# LC_BigOne_-_MainBlock.net
KiCad netlist of a schematic drawn in Altium Designer
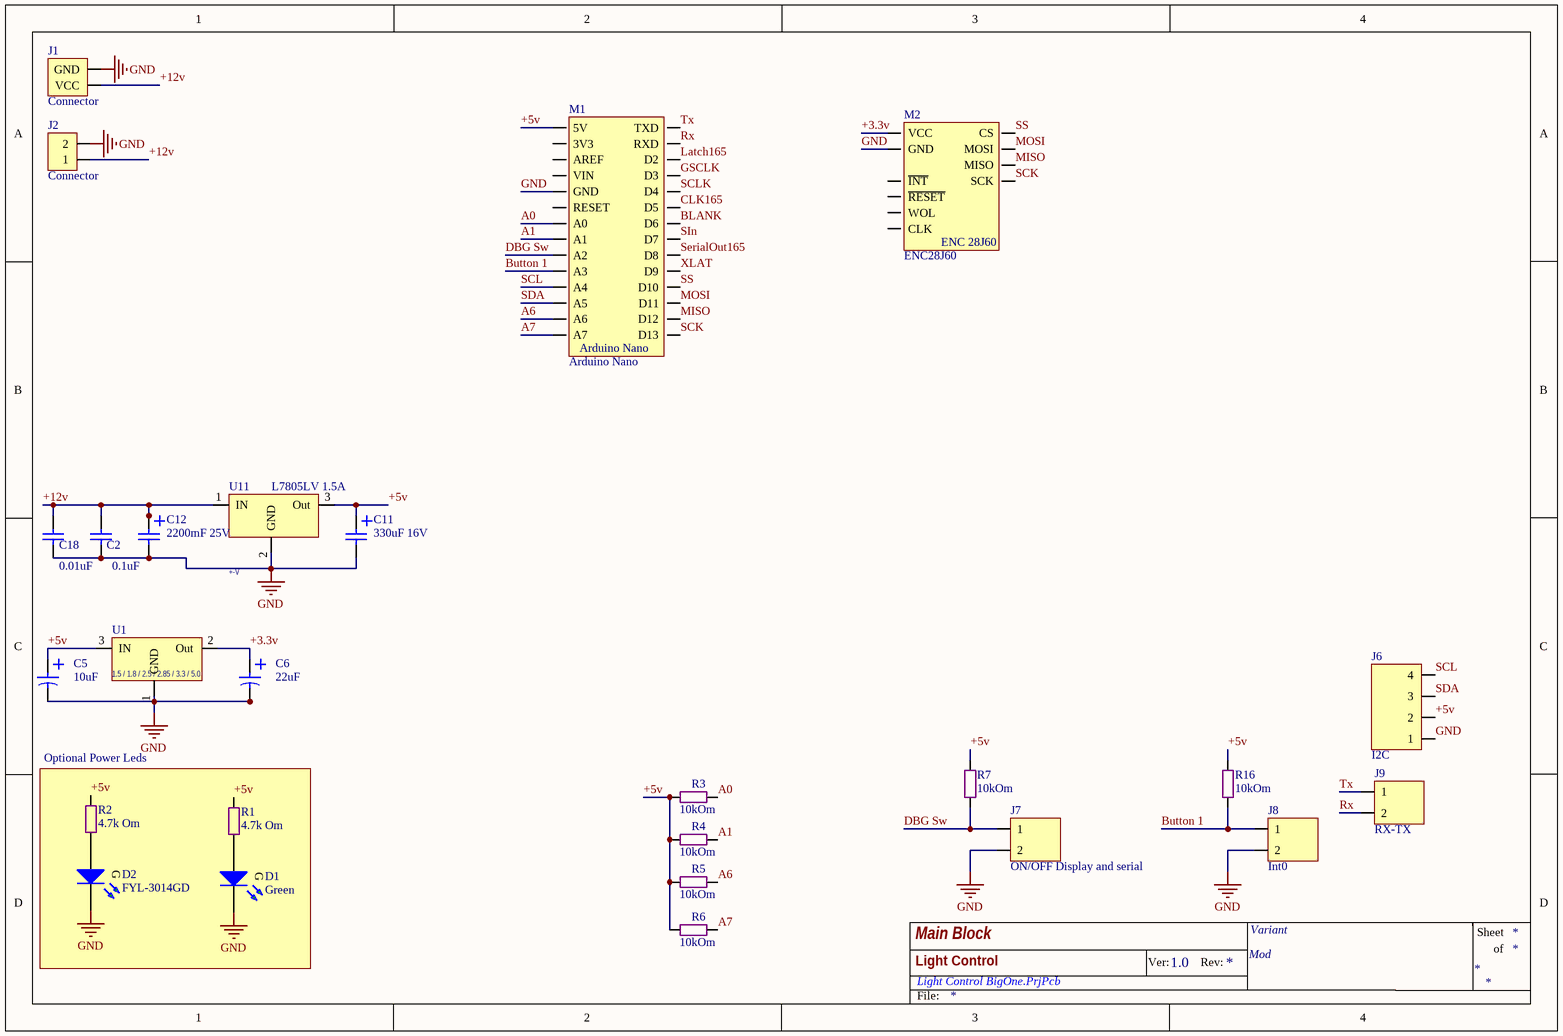
[diagram p0: LC BigOne - MainBlock.SchDoc]

(export (version "E")
  (design (tool "Eeschema 10.0.6"))
  (components
    (comp (ref "C2")
      (value "0.1uF")
      (footprint "Capacitor:SMD 0805 (2012)")
      (description "Capacitor")
      (libsource (lib "Capacitor") (part "Cap SMD 0402-1812"))
    )
    (comp (ref "C5")
      (value "10uF")
      (footprint "Capacitor:SMD 1206 Tantal (3216)")
      (description "Capacitor")
      (libsource (lib "Capacitor") (part "Cap Tantal"))
    )
    (comp (ref "C6")
      (value "22uF")
      (footprint "Capacitor:SMD 3528 Tantal (1210)")
      (description "Capacitor")
      (libsource (lib "Capacitor") (part "Cap Tantal"))
    )
    (comp (ref "C11")
      (value "330uF 16V")
      (footprint "Capacitor:Cap E p3.5mm D8xH12")
      (description "Capacitor")
      (libsource (lib "Capacitor") (part "Cap E 330uF x 16V"))
    )
    (comp (ref "C12")
      (value "2200mF 25V")
      (footprint "Capacitor:Cap E p5.08mm D10.2mm (3p) R")
      (description "Capacitor")
      (libsource (lib "Capacitor") (part "Cap E 2200mF x 16V"))
    )
    (comp (ref "C18")
      (value "0.01uF")
      (footprint "Capacitor:SMD 0805 (2012)")
      (description "Capacitor")
      (libsource (lib "Capacitor") (part "Cap SMD 0402-1812"))
    )
    (comp (ref "D1")
      (value "Green")
      (footprint "LED:LED SMD 0805 Green")
      (description "?2v ?20mA")
      (libsource (lib "LED") (part "Led SMD Green"))
    )
    (comp (ref "D2")
      (value "FYL-3014GD")
      (footprint "LED:LED Round 3mm Green")
      (description "2.1v 10mA, 15-30mCd")
      (libsource (lib "LED") (part "Led Round 3mm Green"))
    )
    (comp (ref "J1")
      (value "Connector")
      (footprint "Connector:DC Connector")
      (description "DC Connector")
      (libsource (lib "Connector") (part "DC Connector (PJ-002B)"))
    )
    (comp (ref "J2")
      (value "Connector")
      (footprint "Connector:DG301 5mm 2p")
      (description "DG301 series")
      (libsource (lib "Connector") (part "DG301-5.0-2P12"))
    )
    (comp (ref "J6")
      (value "I2C")
      (footprint "Connector:Line 2.54 X 4")
      (description "Vert, Sgl line, Male")
      (libsource (lib "Connector") (part "PLS-4"))
    )
    (comp (ref "J7")
      (value "ON/OFF Display and serial")
      (footprint "Connector:Line 2.54 x 2")
      (description "Vert, Sgl line, Male")
      (libsource (lib "Connector") (part "PLS-2"))
    )
    (comp (ref "J8")
      (value "Int0")
      (footprint "Connector:Line 2.54 x 2")
      (description "Vert, Sgl line, Male")
      (libsource (lib "Connector") (part "PLS-2"))
    )
    (comp (ref "J9")
      (value "RX-TX")
      (footprint "Connector:Line 2.54 x 2")
      (description "Vert, Sgl line, Male")
      (libsource (lib "Connector") (part "PLS-2"))
    )
    (comp (ref "M1")
      (value "Arduino Nano")
      (footprint "Modules:Arduino Nano")
      (libsource (lib "Modules") (part "Arduino Nano"))
    )
    (comp (ref "M2")
      (value "ENC28J60")
      (footprint "Modules:ENC28J60 MiNi")
      (libsource (lib "Modules") (part "ENC28J60"))
    )
    (comp (ref "R1")
      (value "4.7k Om")
      (footprint "PassiveComponents:SMD 0805 (2012)")
      (libsource (lib "PassiveComponents") (part "Res All Types"))
    )
    (comp (ref "R2")
      (value "4.7k Om")
      (footprint "PassiveComponents:SMD 0805 (2012)")
      (libsource (lib "PassiveComponents") (part "Res All Types"))
    )
    (comp (ref "R3")
      (value "10kOm")
      (footprint "PassiveComponents:SMD 0805 (2012)")
      (libsource (lib "PassiveComponents") (part "Res All Types"))
    )
    (comp (ref "R4")
      (value "10kOm")
      (footprint "PassiveComponents:SMD 0805 (2012)")
      (libsource (lib "PassiveComponents") (part "Res All Types"))
    )
    (comp (ref "R5")
      (value "10kOm")
      (footprint "PassiveComponents:SMD 0805 (2012)")
      (libsource (lib "PassiveComponents") (part "Res All Types"))
    )
    (comp (ref "R6")
      (value "10kOm")
      (footprint "PassiveComponents:SMD 0805 (2012)")
      (libsource (lib "PassiveComponents") (part "Res All Types"))
    )
    (comp (ref "R7")
      (value "10kOm")
      (footprint "PassiveComponents:SMD 0805 (2012)")
      (libsource (lib "PassiveComponents") (part "Res All Types"))
    )
    (comp (ref "R16")
      (value "10kOm")
      (footprint "PassiveComponents:SMD 0805 (2012)")
      (libsource (lib "PassiveComponents") (part "Res All Types"))
    )
    (comp (ref "U1")
      (value "AMS1117 1.5 / 1.8 / 2.5 / 2.85 / 3.3 / 5.0")
      (footprint "GeneralCases:SOT-223-3 (AMS)")
      (description "Voltage Regulator SOT-223-3")
      (fields (field (name "V OUT") "1.5 / 1.8 / 2.5 / 2.85 / 3.3 / 5.0"))
      (libsource (lib "PowerAdjusment") (part "AMS1117_FIX"))
    )
    (comp (ref "U11")
      (value "L7805LV 1.5A")
      (footprint "GeneralCases:TO220 L")
      (description "Linear Voltage Regulator")
      (fields (field (name "V OUT") "+-V"))
      (libsource (lib "PowerAdjusment") (part "KPEH"))
    )
  )
  (nets
    (net (code "1") (name "/+3.3v") (class "Default")
      (node (ref "C6") (pin "VCC") (pinfunction "1_VCC") (pintype "passive"))
      (node (ref "M2") (pin "VCC") (pinfunction "VCC_VCC") (pintype "passive"))
      (node (ref "U1") (pin "2") (pinfunction "Out_2") (pintype "power_in"))
    )
    (net (code "2") (name "/+5v") (class "Default")
      (node (ref "C11") (pin "1") (pinfunction "1_1") (pintype "passive"))
      (node (ref "C5") (pin "VCC") (pinfunction "1_VCC") (pintype "passive"))
      (node (ref "J6") (pin "2") (pinfunction "2_2") (pintype "passive"))
      (node (ref "M1") (pin "5V") (pinfunction "5V_5V") (pintype "passive"))
      (node (ref "R1") (pin "1") (pinfunction "1_1") (pintype "passive"))
      (node (ref "R16") (pin "2") (pinfunction "2_2") (pintype "passive"))
      (node (ref "R2") (pin "1") (pinfunction "1_1") (pintype "passive"))
      (node (ref "R3") (pin "2") (pinfunction "2_2") (pintype "passive"))
      (node (ref "R4") (pin "2") (pinfunction "2_2") (pintype "passive"))
      (node (ref "R5") (pin "2") (pinfunction "2_2") (pintype "passive"))
      (node (ref "R6") (pin "2") (pinfunction "2_2") (pintype "passive"))
      (node (ref "R7") (pin "2") (pinfunction "2_2") (pintype "passive"))
      (node (ref "U1") (pin "3") (pinfunction "IN_3") (pintype "power_in"))
      (node (ref "U11") (pin "3") (pinfunction "Out_3") (pintype "power_in"))
    )
    (net (code "3") (name "/+12v") (class "Default")
      (node (ref "C12") (pin "1") (pinfunction "1_1") (pintype "passive"))
      (node (ref "C18") (pin "1") (pinfunction "1_1") (pintype "passive"))
      (node (ref "C2") (pin "1") (pinfunction "1_1") (pintype "passive"))
      (node (ref "J1") (pin "VCC") (pinfunction "VCC_VCC") (pintype "passive"))
      (node (ref "J2") (pin "1") (pinfunction "1_1") (pintype "passive"))
      (node (ref "U11") (pin "1") (pinfunction "IN_1") (pintype "power_in"))
    )
    (net (code "4") (name "/A0") (class "Default")
      (node (ref "M1") (pin "A0") (pinfunction "A0_A0") (pintype "passive"))
      (node (ref "R3") (pin "1") (pinfunction "1_1") (pintype "passive"))
    )
    (net (code "5") (name "/A1") (class "Default")
      (node (ref "M1") (pin "A1") (pinfunction "A1_A1") (pintype "passive"))
      (node (ref "R4") (pin "1") (pinfunction "1_1") (pintype "passive"))
    )
    (net (code "6") (name "/A6") (class "Default")
      (node (ref "M1") (pin "A6") (pinfunction "A6_A6") (pintype "passive"))
      (node (ref "R5") (pin "1") (pinfunction "1_1") (pintype "passive"))
    )
    (net (code "7") (name "/A7") (class "Default")
      (node (ref "M1") (pin "A7") (pinfunction "A7_A7") (pintype "passive"))
      (node (ref "R6") (pin "1") (pinfunction "1_1") (pintype "passive"))
    )
    (net (code "8") (name "/BLANK") (class "Default")
      (node (ref "M1") (pin "D6") (pinfunction "D6_D6") (pintype "passive"))
    )
    (net (code "9") (name "/Button 1") (class "Default")
      (node (ref "J8") (pin "1") (pinfunction "1_1") (pintype "passive"))
      (node (ref "M1") (pin "A3") (pinfunction "A3_A3") (pintype "passive"))
      (node (ref "R16") (pin "1") (pinfunction "1_1") (pintype "passive"))
    )
    (net (code "10") (name "/CLK165") (class "Default")
      (node (ref "M1") (pin "D5") (pinfunction "D5_D5") (pintype "passive"))
    )
    (net (code "11") (name "/DBG Sw") (class "Default")
      (node (ref "J7") (pin "1") (pinfunction "1_1") (pintype "passive"))
      (node (ref "M1") (pin "A2") (pinfunction "A2_A2") (pintype "passive"))
      (node (ref "R7") (pin "1") (pinfunction "1_1") (pintype "passive"))
    )
    (net (code "12") (name "/GSCLK") (class "Default")
      (node (ref "M1") (pin "D3") (pinfunction "D3_D3") (pintype "passive"))
    )
    (net (code "13") (name "/Latch165") (class "Default")
      (node (ref "M1") (pin "D2") (pinfunction "D2_D2") (pintype "passive"))
    )
    (net (code "14") (name "/MISO") (class "Default")
      (node (ref "M1") (pin "D12") (pinfunction "D12_D12") (pintype "passive"))
      (node (ref "M2") (pin "MISO") (pinfunction "MISO_MISO") (pintype "passive"))
    )
    (net (code "15") (name "/MOSI") (class "Default")
      (node (ref "M1") (pin "D11") (pinfunction "D11_D11") (pintype "passive"))
      (node (ref "M2") (pin "MOSI") (pinfunction "MOSI_MOSI") (pintype "passive"))
    )
    (net (code "16") (name "/Rx") (class "Default")
      (node (ref "J9") (pin "2") (pinfunction "2_2") (pintype "passive"))
      (node (ref "M1") (pin "RXD") (pinfunction "RXD_RXD") (pintype "passive"))
    )
    (net (code "17") (name "/SCK") (class "Default")
      (node (ref "M1") (pin "D13") (pinfunction "D13_D13") (pintype "passive"))
      (node (ref "M2") (pin "SCK") (pinfunction "SCK_SCK") (pintype "passive"))
    )
    (net (code "18") (name "/SCL") (class "Default")
      (node (ref "J6") (pin "4") (pinfunction "4_4") (pintype "passive"))
      (node (ref "M1") (pin "A4") (pinfunction "A4_A4") (pintype "passive"))
    )
    (net (code "19") (name "/SCLK") (class "Default")
      (node (ref "M1") (pin "D4") (pinfunction "D4_D4") (pintype "passive"))
    )
    (net (code "20") (name "/SDA") (class "Default")
      (node (ref "J6") (pin "3") (pinfunction "3_3") (pintype "passive"))
      (node (ref "M1") (pin "A5") (pinfunction "A5_A5") (pintype "passive"))
    )
    (net (code "21") (name "/SIn") (class "Default")
      (node (ref "M1") (pin "D7") (pinfunction "D7_D7") (pintype "passive"))
    )
    (net (code "22") (name "/SS") (class "Default")
      (node (ref "M1") (pin "D10") (pinfunction "D10_D10") (pintype "passive"))
      (node (ref "M2") (pin "CS") (pinfunction "CS_CS") (pintype "passive"))
    )
    (net (code "23") (name "/SerialOut165") (class "Default")
      (node (ref "M1") (pin "D8") (pinfunction "D8_D8") (pintype "passive"))
    )
    (net (code "24") (name "/Tx") (class "Default")
      (node (ref "J9") (pin "1") (pinfunction "1_1") (pintype "passive"))
      (node (ref "M1") (pin "TXD") (pinfunction "TXD_TXD") (pintype "passive"))
    )
    (net (code "25") (name "/XLAT") (class "Default")
      (node (ref "M1") (pin "D9") (pinfunction "D9_D9") (pintype "passive"))
    )
    (net (code "26") (name "GND") (class "Default")
      (node (ref "C11") (pin "2") (pinfunction "2_2") (pintype "passive"))
      (node (ref "C12") (pin "2") (pinfunction "2_2") (pintype "passive"))
      (node (ref "C18") (pin "2") (pinfunction "2_2") (pintype "passive"))
      (node (ref "C2") (pin "2") (pinfunction "2_2") (pintype "passive"))
      (node (ref "C5") (pin "GND") (pinfunction "2_GND") (pintype "passive"))
      (node (ref "C6") (pin "GND") (pinfunction "2_GND") (pintype "passive"))
      (node (ref "D1") (pin "K") (pinfunction "K_K") (pintype "passive"))
      (node (ref "D2") (pin "K") (pinfunction "K_K") (pintype "passive"))
      (node (ref "J1") (pin "GND") (pinfunction "GND_GND") (pintype "passive"))
      (node (ref "J2") (pin "2") (pinfunction "2_2") (pintype "passive"))
      (node (ref "J6") (pin "1") (pinfunction "1_1") (pintype "passive"))
      (node (ref "J7") (pin "2") (pinfunction "2_2") (pintype "passive"))
      (node (ref "J8") (pin "2") (pinfunction "2_2") (pintype "passive"))
      (node (ref "M1") (pin "GND") (pinfunction "GND_GND") (pintype "passive"))
      (node (ref "M2") (pin "GND") (pinfunction "GND_GND") (pintype "passive"))
      (node (ref "U1") (pin "1") (pinfunction "GND_1") (pintype "passive"))
      (node (ref "U11") (pin "2") (pinfunction "GND_2") (pintype "passive"))
    )
    (net (code "27") (name "Net-(D1-PadA)") (class "Default")
      (node (ref "D1") (pin "A") (pinfunction "A_A") (pintype "passive"))
      (node (ref "R1") (pin "2") (pinfunction "2_2") (pintype "passive"))
    )
    (net (code "28") (name "Net-(D2-PadA)") (class "Default")
      (node (ref "D2") (pin "A") (pinfunction "A_A") (pintype "passive"))
      (node (ref "R2") (pin "2") (pinfunction "2_2") (pintype "passive"))
    )
    (net (code "29") (name "unconnected-(M1-Pad3V3)") (class "Default")
      (node (ref "M1") (pin "3V3") (pinfunction "3V3_3V3") (pintype "passive"))
    )
    (net (code "30") (name "unconnected-(M1-PadAREF)") (class "Default")
      (node (ref "M1") (pin "AREF") (pinfunction "AREF_AREF") (pintype "passive"))
    )
    (net (code "31") (name "unconnected-(M1-PadRESET)") (class "Default")
      (node (ref "M1") (pin "RESET") (pinfunction "RESET_RESET") (pintype "passive"))
    )
    (net (code "32") (name "unconnected-(M1-PadVIN)") (class "Default")
      (node (ref "M1") (pin "VIN") (pinfunction "VIN_VIN") (pintype "passive"))
    )
    (net (code "33") (name "unconnected-(M2-PadCLK)") (class "Default")
      (node (ref "M2") (pin "CLK") (pinfunction "CLK_CLK") (pintype "passive"))
    )
    (net (code "34") (name "unconnected-(M2-PadWOL)") (class "Default")
      (node (ref "M2") (pin "WOL") (pinfunction "WOL_WOL") (pintype "passive"))
    )
    (net (code "35") (name "unconnected-(M2-~{INT}-PadINT)") (class "Default")
      (node (ref "M2") (pin "INT") (pinfunction "~{INT}_INT") (pintype "passive"))
    )
    (net (code "36") (name "unconnected-(M2-~{RESET}-PadRESET)") (class "Default")
      (node (ref "M2") (pin "RESET") (pinfunction "~{RESET}_RESET") (pintype "passive"))
    )
  )
)
